# v2nixie.net
KiCad netlist of a schematic drawn in EAGLE
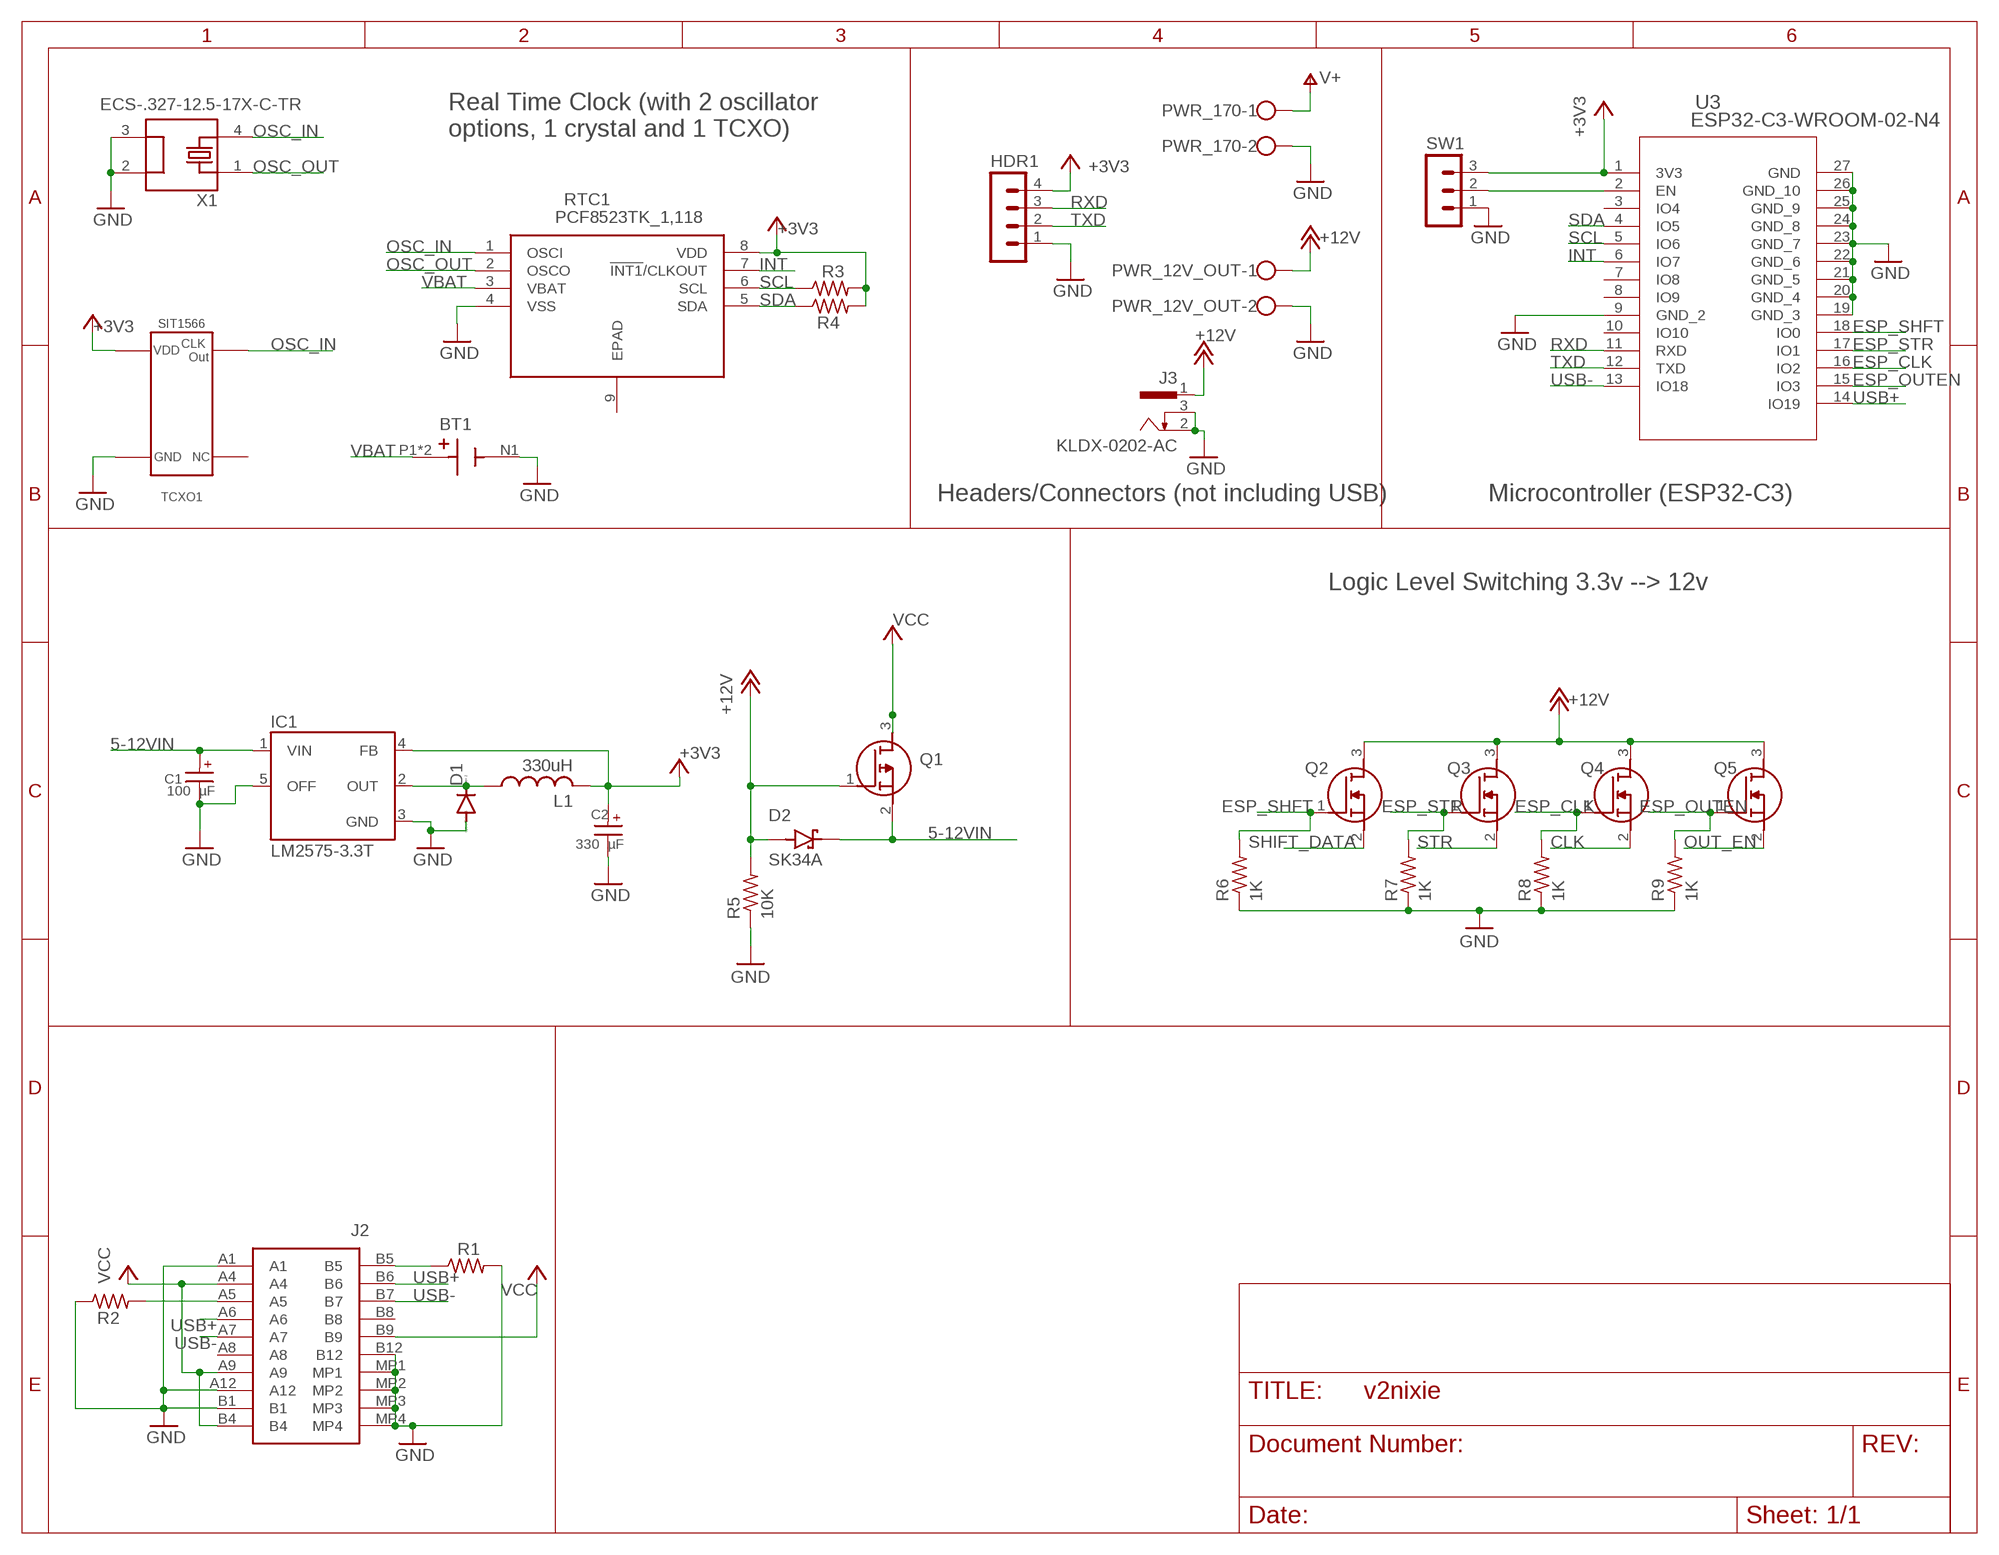
[diagram p0: schematic, sheet 1, part 1 of 2]
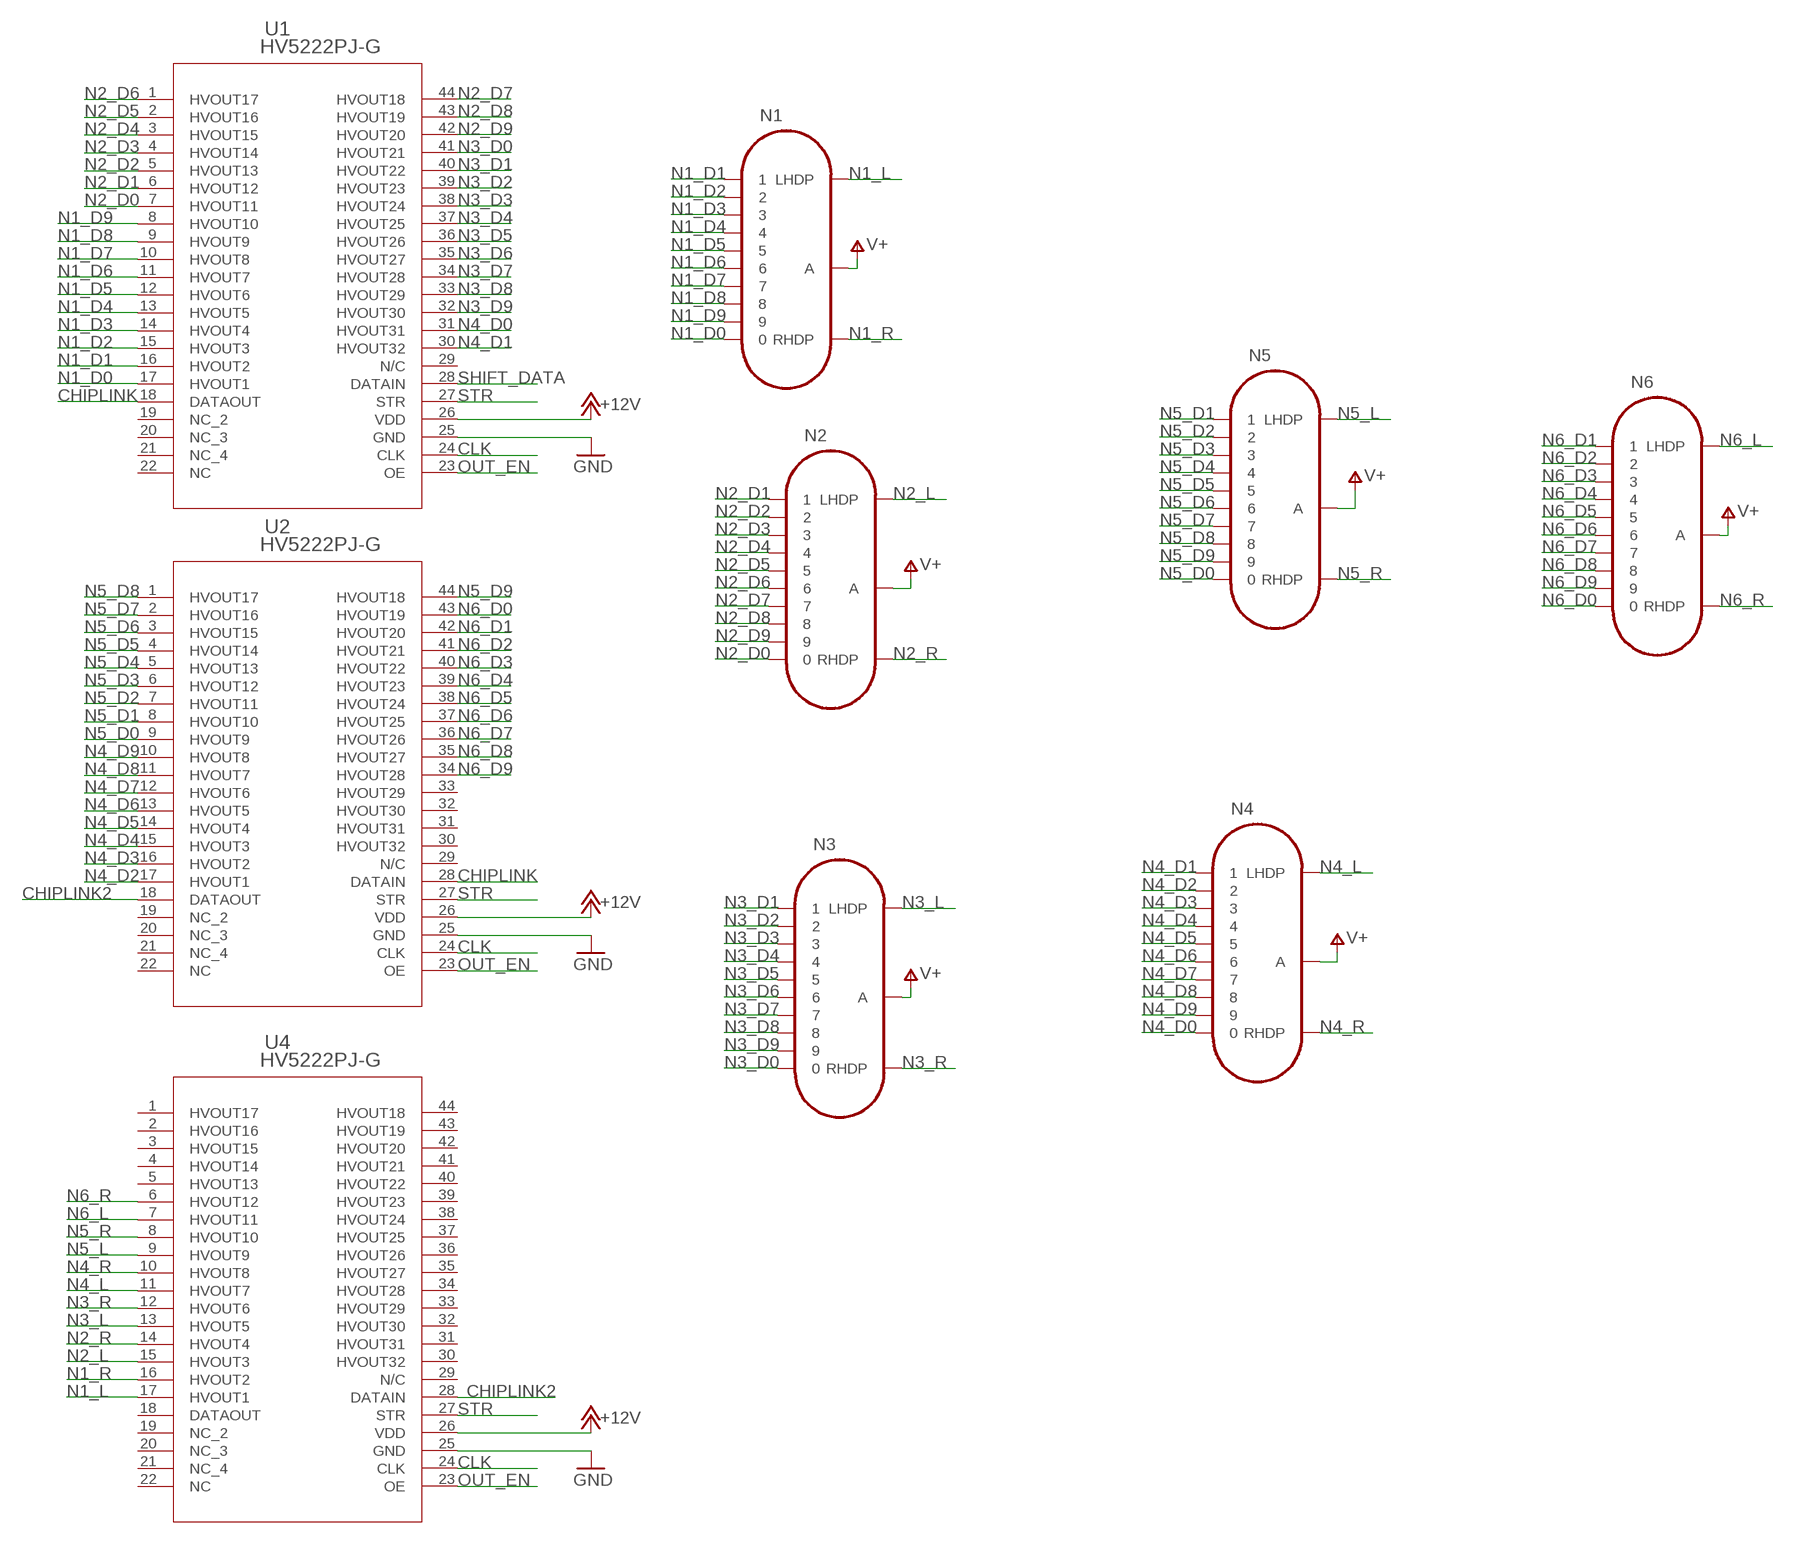
[diagram p1: schematic, sheet 1, part 2 of 2]

(export (version "E")
  (design (tool "Eeschema 10.0.6"))
  (components
    (comp (ref "BT1")
      (value "BAT-HLD-001-TR")
      (footprint "eagle-import:BAT_BAT-HLD-001-TR")
      (fields
        (field (name "DIGI-KEY_PART_NUMBER") "BAT-HLD-001-TRTR-ND")
        (field (name "MF") "Linx Technologies")
      )
      (libsource (lib "eagle-import") (part "BAT-HLD-001-TR"))
    )
    (comp (ref "C1")
      (value "100 µF")
      (footprint "eagle-import:WCAP-PTG5_8X11.5(DXL)")
      (libsource (lib "eagle-import") (part "WCAP-PTG5_8X11.5_870025374001"))
    )
    (comp (ref "C2")
      (value "330 µF")
      (footprint "eagle-import:WCAP-PTG5_8X8(DXL)")
      (libsource (lib "eagle-import") (part "WCAP-PTG5_8X8_870025174004"))
    )
    (comp (ref "D1")
      (value "DIODE-DO201-15")
      (footprint "eagle-import:DO201-15")
      (libsource (lib "eagle-import") (part "DIODE-DO201-15"))
    )
    (comp (ref "D2")
      (value "SK34A")
      (footprint "eagle-import:DIOM4325X250N")
      (fields (field (name "MF") "Taiwan Semiconductor") (field (name "MP") "SK34A-T"))
      (libsource (lib "eagle-import") (part "SK34A"))
    )
    (comp (ref "HDR1")
      (value "MA04-1")
      (footprint "eagle-import:MA04-1")
      (libsource (lib "eagle-import") (part "MA04-1"))
    )
    (comp (ref "IC1")
      (value "LM2575-3.3T")
      (footprint "eagle-import:TO220-5")
      (libsource (lib "eagle-import") (part "LM2575-3.3T"))
    )
    (comp (ref "J2")
      (value "USB4110-GF-A")
      (footprint "eagle-import:USB4110GFA")
      (fields (field (name "MOUSER_PART_NUMBER") "640-USB4110-GF-A"))
      (libsource (lib "eagle-import") (part "USB4110-GF-A"))
    )
    (comp (ref "J3")
      (value "KLDX-0202-AC")
      (footprint "eagle-import:KYCON_KLDX-0202-AC")
      (fields (field (name "DIGI-KEY_PART_NUMBER") "2092-KLDX-0202-AC-ND") (field (name "MF") "Kycon"))
      (libsource (lib "eagle-import") (part "KLDX-0202-AC"))
    )
    (comp (ref "L1")
      (value "330uH")
      (footprint "eagle-import:6000-XXXX-RC")
      (libsource (lib "eagle-import") (part "L-US6000-XXX-RC"))
    )
    (comp (ref "N1")
      (value "IN-14")
      (footprint "eagle-import:IN-14")
      (libsource (lib "eagle-import") (part "IN-14"))
    )
    (comp (ref "N2")
      (value "IN-14")
      (footprint "eagle-import:IN-14")
      (libsource (lib "eagle-import") (part "IN-14"))
    )
    (comp (ref "N3")
      (value "IN-14")
      (footprint "eagle-import:IN-14")
      (libsource (lib "eagle-import") (part "IN-14"))
    )
    (comp (ref "N4")
      (value "IN-14")
      (footprint "eagle-import:IN-14")
      (libsource (lib "eagle-import") (part "IN-14"))
    )
    (comp (ref "N5")
      (value "IN-14")
      (footprint "eagle-import:IN-14")
      (libsource (lib "eagle-import") (part "IN-14"))
    )
    (comp (ref "N6")
      (value "IN-14")
      (footprint "eagle-import:IN-14")
      (libsource (lib "eagle-import") (part "IN-14"))
    )
    (comp (ref "PWR_12V_OUT")
      (value "W237-102")
      (footprint "eagle-import:W237-102")
      (fields (field (name "MPN") "237-102") (field (name "SPICEPREFIX") "X"))
      (libsource (lib "eagle-import") (part "W237-102"))
    )
    (comp (ref "PWR_170")
      (value "W237-102")
      (footprint "eagle-import:W237-102")
      (fields (field (name "MPN") "237-102") (field (name "SPICEPREFIX") "X"))
      (libsource (lib "eagle-import") (part "W237-102"))
    )
    (comp (ref "Q1")
      (value "SSM3J117TU,LF_T")
      (footprint "eagle-import:SSM3J117TULFT")
      (fields (field (name "MANUFACTURER_PART_NUMBER") "SSM3J117TU,LF(T"))
      (libsource (lib "eagle-import") (part "SSM3J117TU,LF_T"))
    )
    (comp (ref "Q2")
      (value "RU1J002YNTCL")
      (footprint "eagle-import:SOTFL65P210X105-3N")
      (fields (field (name "MOUSER_PART_NUMBER") "755-RU1J002YNTCL"))
      (libsource (lib "eagle-import") (part "RU1J002YNTCL"))
    )
    (comp (ref "Q3")
      (value "RU1J002YNTCL")
      (footprint "eagle-import:SOTFL65P210X105-3N")
      (fields (field (name "MOUSER_PART_NUMBER") "755-RU1J002YNTCL"))
      (libsource (lib "eagle-import") (part "RU1J002YNTCL"))
    )
    (comp (ref "Q4")
      (value "RU1J002YNTCL")
      (footprint "eagle-import:SOTFL65P210X105-3N")
      (fields (field (name "MOUSER_PART_NUMBER") "755-RU1J002YNTCL"))
      (libsource (lib "eagle-import") (part "RU1J002YNTCL"))
    )
    (comp (ref "Q5")
      (value "RU1J002YNTCL")
      (footprint "eagle-import:SOTFL65P210X105-3N")
      (fields (field (name "MOUSER_PART_NUMBER") "755-RU1J002YNTCL"))
      (libsource (lib "eagle-import") (part "RU1J002YNTCL"))
    )
    (comp (ref "R1")
      (value "5.1K")
      (footprint "eagle-import:R0805")
      (libsource (lib "eagle-import") (part "R-US_R0805"))
    )
    (comp (ref "R2")
      (value "5.1K")
      (footprint "eagle-import:R0805")
      (libsource (lib "eagle-import") (part "R-US_R0805"))
    )
    (comp (ref "R3")
      (value "10K")
      (footprint "eagle-import:R0805")
      (libsource (lib "eagle-import") (part "R-US_R0805"))
    )
    (comp (ref "R4")
      (value "10K")
      (footprint "eagle-import:R0805")
      (libsource (lib "eagle-import") (part "R-US_R0805"))
    )
    (comp (ref "R5")
      (value "10K")
      (footprint "eagle-import:M0805")
      (libsource (lib "eagle-import") (part "resistor_348_R-US_M0805"))
    )
    (comp (ref "R6")
      (value "1K")
      (footprint "eagle-import:M0805")
      (libsource (lib "eagle-import") (part "resistor_348_R-US_M0805"))
    )
    (comp (ref "R7")
      (value "1K")
      (footprint "eagle-import:M0805")
      (libsource (lib "eagle-import") (part "resistor_348_R-US_M0805"))
    )
    (comp (ref "R8")
      (value "1K")
      (footprint "eagle-import:M0805")
      (libsource (lib "eagle-import") (part "resistor_348_R-US_M0805"))
    )
    (comp (ref "R9")
      (value "1K")
      (footprint "eagle-import:M0805")
      (libsource (lib "eagle-import") (part "resistor_348_R-US_M0805"))
    )
    (comp (ref "RTC1")
      (value "PCF8523TK_1,118")
      (footprint "eagle-import:SON80P400X400X100-9N")
      (fields
        (field (name "MANUFACTURER_PART_NUMBER") "PCF8523TK/1,118")
        (field (name "MOUSER_PART_NUMBER") "771-PCF8523TK/1118")
      )
      (libsource (lib "eagle-import") (part "PCF8523TK_1,118"))
    )
    (comp (ref "SW1")
      (value "MA03-1")
      (footprint "eagle-import:MA03-1")
      (libsource (lib "eagle-import") (part "MA03-1"))
    )
    (comp (ref "TCXO1")
      (value "SIT1566")
      (footprint "eagle-import:SIT1566")
      (libsource (lib "eagle-import") (part "SIT1566"))
    )
    (comp (ref "U1")
      (value "HV5222PJ-G")
      (footprint "eagle-import:PLCC44_MC_MCH")
      (fields (field (name "COPYRIGHT") "Copyright (C) 2022 Ultra Librarian. All rights reserved."))
      (libsource (lib "eagle-import") (part "HV5222PJ-G"))
    )
    (comp (ref "U2")
      (value "HV5222PJ-G")
      (footprint "eagle-import:PLCC44_MC_MCH")
      (fields (field (name "COPYRIGHT") "Copyright (C) 2022 Ultra Librarian. All rights reserved."))
      (libsource (lib "eagle-import") (part "HV5222PJ-G"))
    )
    (comp (ref "U3")
      (value "ESP32-C3-WROOM-02-N4")
      (footprint "eagle-import:IC18_ESP32-C3-WROOM-02-N4_EXP")
      (fields (field (name "COPYRIGHT") "Copyright (C) 2022 Ultra Librarian. All rights reserved."))
      (libsource (lib "eagle-import") (part "ESP32-C3-WROOM-02-N4"))
    )
    (comp (ref "U4")
      (value "HV5222PJ-G")
      (footprint "eagle-import:PLCC44_MC_MCH")
      (fields (field (name "COPYRIGHT") "Copyright (C) 2022 Ultra Librarian. All rights reserved."))
      (libsource (lib "eagle-import") (part "HV5222PJ-G"))
    )
    (comp (ref "X1")
      (value "ECS-.327-12.5-17X-C-TR")
      (footprint "eagle-import:XTAL_ECS-.327-12.5-17X-C-TR")
      (fields (field (name "DIGI-KEY_PART_NUMBER") "XC1912TR-ND") (field (name "MF") "ECS Inc."))
      (libsource (lib "eagle-import") (part "ECS-.327-12.5-17X-C-TR"))
    )
  )
  (nets
    (net (code "1") (name "+3V3") (class "Default")
      (node (ref "C2") (pin "1") (pinfunction "+_1") (pintype "passive"))
      (node (ref "HDR1") (pin "4") (pinfunction "4_4") (pintype "passive"))
      (node (ref "IC1") (pin "4") (pinfunction "FB_4") (pintype "input"))
      (node (ref "L1") (pin "2") (pinfunction "2_2") (pintype "passive"))
      (node (ref "R3") (pin "2") (pinfunction "2_2") (pintype "passive"))
      (node (ref "R4") (pin "2") (pinfunction "2_2") (pintype "passive"))
      (node (ref "RTC1") (pin "8") (pinfunction "VDD_8") (pintype "bidirectional"))
      (node (ref "SW1") (pin "3") (pinfunction "3_3") (pintype "passive"))
      (node (ref "TCXO1") (pin "VDD") (pinfunction "VDD_VDD") (pintype "power_in"))
      (node (ref "U3") (pin "1") (pinfunction "3V3_1") (pintype "passive"))
    )
    (net (code "2") (name "+12V") (class "Default")
      (node (ref "D2") (pin "A") (pinfunction "A_A") (pintype "passive"))
      (node (ref "J3") (pin "1") (pinfunction "1_1") (pintype "passive"))
      (node (ref "PWR_12V_OUT") (pin "1") (pinfunction "KL_1") (pintype "passive"))
      (node (ref "Q1") (pin "1") (pinfunction "G_1") (pintype "bidirectional"))
      (node (ref "Q2") (pin "3") (pinfunction "D_3") (pintype "bidirectional"))
      (node (ref "Q3") (pin "3") (pinfunction "D_3") (pintype "bidirectional"))
      (node (ref "Q4") (pin "3") (pinfunction "D_3") (pintype "bidirectional"))
      (node (ref "Q5") (pin "3") (pinfunction "D_3") (pintype "bidirectional"))
      (node (ref "R5") (pin "2") (pinfunction "2_2") (pintype "passive"))
      (node (ref "U1") (pin "26") (pinfunction "VDD_26") (pintype "power_in"))
      (node (ref "U2") (pin "26") (pinfunction "VDD_26") (pintype "power_in"))
      (node (ref "U4") (pin "26") (pinfunction "VDD_26") (pintype "power_in"))
    )
    (net (code "3") (name "/5-12VIN") (class "Default")
      (node (ref "C1") (pin "1") (pinfunction "+_1") (pintype "passive"))
      (node (ref "D2") (pin "C") (pinfunction "K_C") (pintype "passive"))
      (node (ref "IC1") (pin "1") (pinfunction "VIN_1") (pintype "power_in"))
      (node (ref "Q1") (pin "2") (pinfunction "S_2") (pintype "bidirectional"))
    )
    (net (code "4") (name "/CHIPLINK") (class "Default")
      (node (ref "U1") (pin "18") (pinfunction "DATAOUT_18") (pintype "output"))
      (node (ref "U2") (pin "28") (pinfunction "DATAIN_28") (pintype "input"))
    )
    (net (code "5") (name "/CHIPLINK2") (class "Default")
      (node (ref "U2") (pin "18") (pinfunction "DATAOUT_18") (pintype "output"))
      (node (ref "U4") (pin "28") (pinfunction "DATAIN_28") (pintype "input"))
    )
    (net (code "6") (name "/CLK") (class "Default")
      (node (ref "Q4") (pin "2") (pinfunction "S_2") (pintype "bidirectional"))
      (node (ref "U1") (pin "24") (pinfunction "CLK_24") (pintype "input"))
      (node (ref "U2") (pin "24") (pinfunction "CLK_24") (pintype "input"))
      (node (ref "U4") (pin "24") (pinfunction "CLK_24") (pintype "input"))
    )
    (net (code "7") (name "/ESP_CLK") (class "Default")
      (node (ref "Q4") (pin "1") (pinfunction "G_1") (pintype "bidirectional"))
      (node (ref "R8") (pin "2") (pinfunction "2_2") (pintype "passive"))
      (node (ref "U3") (pin "16") (pinfunction "IO2_16") (pintype "bidirectional"))
    )
    (net (code "8") (name "/ESP_OUTEN") (class "Default")
      (node (ref "Q5") (pin "1") (pinfunction "G_1") (pintype "bidirectional"))
      (node (ref "R9") (pin "2") (pinfunction "2_2") (pintype "passive"))
      (node (ref "U3") (pin "15") (pinfunction "IO3_15") (pintype "bidirectional"))
    )
    (net (code "9") (name "/ESP_SHFT") (class "Default")
      (node (ref "Q2") (pin "1") (pinfunction "G_1") (pintype "bidirectional"))
      (node (ref "R6") (pin "2") (pinfunction "2_2") (pintype "passive"))
      (node (ref "U3") (pin "18") (pinfunction "IO0_18") (pintype "bidirectional"))
    )
    (net (code "10") (name "/ESP_STR") (class "Default")
      (node (ref "Q3") (pin "1") (pinfunction "G_1") (pintype "bidirectional"))
      (node (ref "R7") (pin "2") (pinfunction "2_2") (pintype "passive"))
      (node (ref "U3") (pin "17") (pinfunction "IO1_17") (pintype "bidirectional"))
    )
    (net (code "11") (name "/INT") (class "Default")
      (node (ref "RTC1") (pin "7") (pinfunction "~{INT1}/CLKOUT_7") (pintype "bidirectional"))
      (node (ref "U3") (pin "6") (pinfunction "IO7_6") (pintype "bidirectional"))
    )
    (net (code "12") (name "/N1_D0") (class "Default")
      (node (ref "N1") (pin "0") (pinfunction "0_0") (pintype "bidirectional"))
      (node (ref "U1") (pin "17") (pinfunction "HVOUT1_17") (pintype "output"))
    )
    (net (code "13") (name "/N1_D1") (class "Default")
      (node (ref "N1") (pin "1") (pinfunction "1_1") (pintype "bidirectional"))
      (node (ref "U1") (pin "16") (pinfunction "HVOUT2_16") (pintype "output"))
    )
    (net (code "14") (name "/N1_D2") (class "Default")
      (node (ref "N1") (pin "2") (pinfunction "2_2") (pintype "bidirectional"))
      (node (ref "U1") (pin "15") (pinfunction "HVOUT3_15") (pintype "output"))
    )
    (net (code "15") (name "/N1_D3") (class "Default")
      (node (ref "N1") (pin "3") (pinfunction "3_3") (pintype "bidirectional"))
      (node (ref "U1") (pin "14") (pinfunction "HVOUT4_14") (pintype "output"))
    )
    (net (code "16") (name "/N1_D4") (class "Default")
      (node (ref "N1") (pin "4") (pinfunction "4_4") (pintype "bidirectional"))
      (node (ref "U1") (pin "13") (pinfunction "HVOUT5_13") (pintype "output"))
    )
    (net (code "17") (name "/N1_D5") (class "Default")
      (node (ref "N1") (pin "5") (pinfunction "5_5") (pintype "bidirectional"))
      (node (ref "U1") (pin "12") (pinfunction "HVOUT6_12") (pintype "output"))
    )
    (net (code "18") (name "/N1_D6") (class "Default")
      (node (ref "N1") (pin "6") (pinfunction "6_6") (pintype "bidirectional"))
      (node (ref "U1") (pin "11") (pinfunction "HVOUT7_11") (pintype "output"))
    )
    (net (code "19") (name "/N1_D7") (class "Default")
      (node (ref "N1") (pin "7") (pinfunction "7_7") (pintype "bidirectional"))
      (node (ref "U1") (pin "10") (pinfunction "HVOUT8_10") (pintype "output"))
    )
    (net (code "20") (name "/N1_D8") (class "Default")
      (node (ref "N1") (pin "8") (pinfunction "8_8") (pintype "bidirectional"))
      (node (ref "U1") (pin "9") (pinfunction "HVOUT9_9") (pintype "output"))
    )
    (net (code "21") (name "/N1_D9") (class "Default")
      (node (ref "N1") (pin "9") (pinfunction "9_9") (pintype "bidirectional"))
      (node (ref "U1") (pin "8") (pinfunction "HVOUT10_8") (pintype "output"))
    )
    (net (code "22") (name "/N1_L") (class "Default")
      (node (ref "N1") (pin "LHDP") (pinfunction "LHDP_LHDP") (pintype "bidirectional"))
      (node (ref "U4") (pin "17") (pinfunction "HVOUT1_17") (pintype "output"))
    )
    (net (code "23") (name "/N1_R") (class "Default")
      (node (ref "N1") (pin "RHDP") (pinfunction "RHDP_RHDP") (pintype "bidirectional"))
      (node (ref "U4") (pin "16") (pinfunction "HVOUT2_16") (pintype "output"))
    )
    (net (code "24") (name "/N2_D0") (class "Default")
      (node (ref "N2") (pin "0") (pinfunction "0_0") (pintype "bidirectional"))
      (node (ref "U1") (pin "7") (pinfunction "HVOUT11_7") (pintype "output"))
    )
    (net (code "25") (name "/N2_D1") (class "Default")
      (node (ref "N2") (pin "1") (pinfunction "1_1") (pintype "bidirectional"))
      (node (ref "U1") (pin "6") (pinfunction "HVOUT12_6") (pintype "output"))
    )
    (net (code "26") (name "/N2_D2") (class "Default")
      (node (ref "N2") (pin "2") (pinfunction "2_2") (pintype "bidirectional"))
      (node (ref "U1") (pin "5") (pinfunction "HVOUT13_5") (pintype "output"))
    )
    (net (code "27") (name "/N2_D3") (class "Default")
      (node (ref "N2") (pin "3") (pinfunction "3_3") (pintype "bidirectional"))
      (node (ref "U1") (pin "4") (pinfunction "HVOUT14_4") (pintype "output"))
    )
    (net (code "28") (name "/N2_D4") (class "Default")
      (node (ref "N2") (pin "4") (pinfunction "4_4") (pintype "bidirectional"))
      (node (ref "U1") (pin "3") (pinfunction "HVOUT15_3") (pintype "output"))
    )
    (net (code "29") (name "/N2_D5") (class "Default")
      (node (ref "N2") (pin "5") (pinfunction "5_5") (pintype "bidirectional"))
      (node (ref "U1") (pin "2") (pinfunction "HVOUT16_2") (pintype "output"))
    )
    (net (code "30") (name "/N2_D6") (class "Default")
      (node (ref "N2") (pin "6") (pinfunction "6_6") (pintype "bidirectional"))
      (node (ref "U1") (pin "1") (pinfunction "HVOUT17_1") (pintype "output"))
    )
    (net (code "31") (name "/N2_D7") (class "Default")
      (node (ref "N2") (pin "7") (pinfunction "7_7") (pintype "bidirectional"))
      (node (ref "U1") (pin "44") (pinfunction "HVOUT18_44") (pintype "output"))
    )
    (net (code "32") (name "/N2_D8") (class "Default")
      (node (ref "N2") (pin "8") (pinfunction "8_8") (pintype "bidirectional"))
      (node (ref "U1") (pin "43") (pinfunction "HVOUT19_43") (pintype "output"))
    )
    (net (code "33") (name "/N2_D9") (class "Default")
      (node (ref "N2") (pin "9") (pinfunction "9_9") (pintype "bidirectional"))
      (node (ref "U1") (pin "42") (pinfunction "HVOUT20_42") (pintype "output"))
    )
    (net (code "34") (name "/N2_L") (class "Default")
      (node (ref "N2") (pin "LHDP") (pinfunction "LHDP_LHDP") (pintype "bidirectional"))
      (node (ref "U4") (pin "15") (pinfunction "HVOUT3_15") (pintype "output"))
    )
    (net (code "35") (name "/N2_R") (class "Default")
      (node (ref "N2") (pin "RHDP") (pinfunction "RHDP_RHDP") (pintype "bidirectional"))
      (node (ref "U4") (pin "14") (pinfunction "HVOUT4_14") (pintype "output"))
    )
    (net (code "36") (name "/N3_D0") (class "Default")
      (node (ref "N3") (pin "0") (pinfunction "0_0") (pintype "bidirectional"))
      (node (ref "U1") (pin "41") (pinfunction "HVOUT21_41") (pintype "output"))
    )
    (net (code "37") (name "/N3_D1") (class "Default")
      (node (ref "N3") (pin "1") (pinfunction "1_1") (pintype "bidirectional"))
      (node (ref "U1") (pin "40") (pinfunction "HVOUT22_40") (pintype "output"))
    )
    (net (code "38") (name "/N3_D2") (class "Default")
      (node (ref "N3") (pin "2") (pinfunction "2_2") (pintype "bidirectional"))
      (node (ref "U1") (pin "39") (pinfunction "HVOUT23_39") (pintype "output"))
    )
    (net (code "39") (name "/N3_D3") (class "Default")
      (node (ref "N3") (pin "3") (pinfunction "3_3") (pintype "bidirectional"))
      (node (ref "U1") (pin "38") (pinfunction "HVOUT24_38") (pintype "output"))
    )
    (net (code "40") (name "/N3_D4") (class "Default")
      (node (ref "N3") (pin "4") (pinfunction "4_4") (pintype "bidirectional"))
      (node (ref "U1") (pin "37") (pinfunction "HVOUT25_37") (pintype "output"))
    )
    (net (code "41") (name "/N3_D5") (class "Default")
      (node (ref "N3") (pin "5") (pinfunction "5_5") (pintype "bidirectional"))
      (node (ref "U1") (pin "36") (pinfunction "HVOUT26_36") (pintype "output"))
    )
    (net (code "42") (name "/N3_D6") (class "Default")
      (node (ref "N3") (pin "6") (pinfunction "6_6") (pintype "bidirectional"))
      (node (ref "U1") (pin "35") (pinfunction "HVOUT27_35") (pintype "output"))
    )
    (net (code "43") (name "/N3_D7") (class "Default")
      (node (ref "N3") (pin "7") (pinfunction "7_7") (pintype "bidirectional"))
      (node (ref "U1") (pin "34") (pinfunction "HVOUT28_34") (pintype "output"))
    )
    (net (code "44") (name "/N3_D8") (class "Default")
      (node (ref "N3") (pin "8") (pinfunction "8_8") (pintype "bidirectional"))
      (node (ref "U1") (pin "33") (pinfunction "HVOUT29_33") (pintype "output"))
    )
    (net (code "45") (name "/N3_D9") (class "Default")
      (node (ref "N3") (pin "9") (pinfunction "9_9") (pintype "bidirectional"))
      (node (ref "U1") (pin "32") (pinfunction "HVOUT30_32") (pintype "output"))
    )
    (net (code "46") (name "/N3_L") (class "Default")
      (node (ref "N3") (pin "LHDP") (pinfunction "LHDP_LHDP") (pintype "bidirectional"))
      (node (ref "U4") (pin "13") (pinfunction "HVOUT5_13") (pintype "output"))
    )
    (net (code "47") (name "/N3_R") (class "Default")
      (node (ref "N3") (pin "RHDP") (pinfunction "RHDP_RHDP") (pintype "bidirectional"))
      (node (ref "U4") (pin "12") (pinfunction "HVOUT6_12") (pintype "output"))
    )
    (net (code "48") (name "/N4_D0") (class "Default")
      (node (ref "N4") (pin "0") (pinfunction "0_0") (pintype "bidirectional"))
      (node (ref "U1") (pin "31") (pinfunction "HVOUT31_31") (pintype "output"))
    )
    (net (code "49") (name "/N4_D1") (class "Default")
      (node (ref "N4") (pin "1") (pinfunction "1_1") (pintype "bidirectional"))
      (node (ref "U1") (pin "30") (pinfunction "HVOUT32_30") (pintype "output"))
    )
    (net (code "50") (name "/N4_D2") (class "Default")
      (node (ref "N4") (pin "2") (pinfunction "2_2") (pintype "bidirectional"))
      (node (ref "U2") (pin "17") (pinfunction "HVOUT1_17") (pintype "output"))
    )
    (net (code "51") (name "/N4_D3") (class "Default")
      (node (ref "N4") (pin "3") (pinfunction "3_3") (pintype "bidirectional"))
      (node (ref "U2") (pin "16") (pinfunction "HVOUT2_16") (pintype "output"))
    )
    (net (code "52") (name "/N4_D4") (class "Default")
      (node (ref "N4") (pin "4") (pinfunction "4_4") (pintype "bidirectional"))
      (node (ref "U2") (pin "15") (pinfunction "HVOUT3_15") (pintype "output"))
    )
    (net (code "53") (name "/N4_D5") (class "Default")
      (node (ref "N4") (pin "5") (pinfunction "5_5") (pintype "bidirectional"))
      (node (ref "U2") (pin "14") (pinfunction "HVOUT4_14") (pintype "output"))
    )
    (net (code "54") (name "/N4_D6") (class "Default")
      (node (ref "N4") (pin "6") (pinfunction "6_6") (pintype "bidirectional"))
      (node (ref "U2") (pin "13") (pinfunction "HVOUT5_13") (pintype "output"))
    )
    (net (code "55") (name "/N4_D7") (class "Default")
      (node (ref "N4") (pin "7") (pinfunction "7_7") (pintype "bidirectional"))
      (node (ref "U2") (pin "12") (pinfunction "HVOUT6_12") (pintype "output"))
    )
    (net (code "56") (name "/N4_D8") (class "Default")
      (node (ref "N4") (pin "8") (pinfunction "8_8") (pintype "bidirectional"))
      (node (ref "U2") (pin "11") (pinfunction "HVOUT7_11") (pintype "output"))
    )
    (net (code "57") (name "/N4_D9") (class "Default")
      (node (ref "N4") (pin "9") (pinfunction "9_9") (pintype "bidirectional"))
      (node (ref "U2") (pin "10") (pinfunction "HVOUT8_10") (pintype "output"))
    )
    (net (code "58") (name "/N4_L") (class "Default")
      (node (ref "N4") (pin "LHDP") (pinfunction "LHDP_LHDP") (pintype "bidirectional"))
      (node (ref "U4") (pin "11") (pinfunction "HVOUT7_11") (pintype "output"))
    )
    (net (code "59") (name "/N4_R") (class "Default")
      (node (ref "N4") (pin "RHDP") (pinfunction "RHDP_RHDP") (pintype "bidirectional"))
      (node (ref "U4") (pin "10") (pinfunction "HVOUT8_10") (pintype "output"))
    )
    (net (code "60") (name "/N5_D0") (class "Default")
      (node (ref "N5") (pin "0") (pinfunction "0_0") (pintype "bidirectional"))
      (node (ref "U2") (pin "9") (pinfunction "HVOUT9_9") (pintype "output"))
    )
    (net (code "61") (name "/N5_D1") (class "Default")
      (node (ref "N5") (pin "1") (pinfunction "1_1") (pintype "bidirectional"))
      (node (ref "U2") (pin "8") (pinfunction "HVOUT10_8") (pintype "output"))
    )
    (net (code "62") (name "/N5_D2") (class "Default")
      (node (ref "N5") (pin "2") (pinfunction "2_2") (pintype "bidirectional"))
      (node (ref "U2") (pin "7") (pinfunction "HVOUT11_7") (pintype "output"))
    )
    (net (code "63") (name "/N5_D3") (class "Default")
      (node (ref "N5") (pin "3") (pinfunction "3_3") (pintype "bidirectional"))
      (node (ref "U2") (pin "6") (pinfunction "HVOUT12_6") (pintype "output"))
    )
    (net (code "64") (name "/N5_D4") (class "Default")
      (node (ref "N5") (pin "4") (pinfunction "4_4") (pintype "bidirectional"))
      (node (ref "U2") (pin "5") (pinfunction "HVOUT13_5") (pintype "output"))
    )
    (net (code "65") (name "/N5_D5") (class "Default")
      (node (ref "N5") (pin "5") (pinfunction "5_5") (pintype "bidirectional"))
      (node (ref "U2") (pin "4") (pinfunction "HVOUT14_4") (pintype "output"))
    )
    (net (code "66") (name "/N5_D6") (class "Default")
      (node (ref "N5") (pin "6") (pinfunction "6_6") (pintype "bidirectional"))
      (node (ref "U2") (pin "3") (pinfunction "HVOUT15_3") (pintype "output"))
    )
    (net (code "67") (name "/N5_D7") (class "Default")
      (node (ref "N5") (pin "7") (pinfunction "7_7") (pintype "bidirectional"))
      (node (ref "U2") (pin "2") (pinfunction "HVOUT16_2") (pintype "output"))
    )
    (net (code "68") (name "/N5_D8") (class "Default")
      (node (ref "N5") (pin "8") (pinfunction "8_8") (pintype "bidirectional"))
      (node (ref "U2") (pin "1") (pinfunction "HVOUT17_1") (pintype "output"))
    )
    (net (code "69") (name "/N5_D9") (class "Default")
      (node (ref "N5") (pin "9") (pinfunction "9_9") (pintype "bidirectional"))
      (node (ref "U2") (pin "44") (pinfunction "HVOUT18_44") (pintype "output"))
    )
    (net (code "70") (name "/N5_L") (class "Default")
      (node (ref "N5") (pin "LHDP") (pinfunction "LHDP_LHDP") (pintype "bidirectional"))
      (node (ref "U4") (pin "9") (pinfunction "HVOUT9_9") (pintype "output"))
    )
    (net (code "71") (name "/N5_R") (class "Default")
      (node (ref "N5") (pin "RHDP") (pinfunction "RHDP_RHDP") (pintype "bidirectional"))
      (node (ref "U4") (pin "8") (pinfunction "HVOUT10_8") (pintype "output"))
    )
    (net (code "72") (name "/N6_D0") (class "Default")
      (node (ref "N6") (pin "0") (pinfunction "0_0") (pintype "bidirectional"))
      (node (ref "U2") (pin "43") (pinfunction "HVOUT19_43") (pintype "output"))
    )
    (net (code "73") (name "/N6_D1") (class "Default")
      (node (ref "N6") (pin "1") (pinfunction "1_1") (pintype "bidirectional"))
      (node (ref "U2") (pin "42") (pinfunction "HVOUT20_42") (pintype "output"))
    )
    (net (code "74") (name "/N6_D2") (class "Default")
      (node (ref "N6") (pin "2") (pinfunction "2_2") (pintype "bidirectional"))
      (node (ref "U2") (pin "41") (pinfunction "HVOUT21_41") (pintype "output"))
    )
    (net (code "75") (name "/N6_D3") (class "Default")
      (node (ref "N6") (pin "3") (pinfunction "3_3") (pintype "bidirectional"))
      (node (ref "U2") (pin "40") (pinfunction "HVOUT22_40") (pintype "output"))
    )
    (net (code "76") (name "/N6_D4") (class "Default")
      (node (ref "N6") (pin "4") (pinfunction "4_4") (pintype "bidirectional"))
      (node (ref "U2") (pin "39") (pinfunction "HVOUT23_39") (pintype "output"))
    )
    (net (code "77") (name "/N6_D5") (class "Default")
      (node (ref "N6") (pin "5") (pinfunction "5_5") (pintype "bidirectional"))
      (node (ref "U2") (pin "38") (pinfunction "HVOUT24_38") (pintype "output"))
    )
    (net (code "78") (name "/N6_D6") (class "Default")
      (node (ref "N6") (pin "6") (pinfunction "6_6") (pintype "bidirectional"))
      (node (ref "U2") (pin "37") (pinfunction "HVOUT25_37") (pintype "output"))
    )
    (net (code "79") (name "/N6_D7") (class "Default")
      (node (ref "N6") (pin "7") (pinfunction "7_7") (pintype "bidirectional"))
      (node (ref "U2") (pin "36") (pinfunction "HVOUT26_36") (pintype "output"))
    )
    (net (code "80") (name "/N6_D8") (class "Default")
      (node (ref "N6") (pin "8") (pinfunction "8_8") (pintype "bidirectional"))
      (node (ref "U2") (pin "35") (pinfunction "HVOUT27_35") (pintype "output"))
    )
    (net (code "81") (name "/N6_D9") (class "Default")
      (node (ref "N6") (pin "9") (pinfunction "9_9") (pintype "bidirectional"))
      (node (ref "U2") (pin "34") (pinfunction "HVOUT28_34") (pintype "output"))
    )
    (net (code "82") (name "/N6_L") (class "Default")
      (node (ref "N6") (pin "LHDP") (pinfunction "LHDP_LHDP") (pintype "bidirectional"))
      (node (ref "U4") (pin "7") (pinfunction "HVOUT11_7") (pintype "output"))
    )
    (net (code "83") (name "/N6_R") (class "Default")
      (node (ref "N6") (pin "RHDP") (pinfunction "RHDP_RHDP") (pintype "bidirectional"))
      (node (ref "U4") (pin "6") (pinfunction "HVOUT12_6") (pintype "output"))
    )
    (net (code "84") (name "/OSC_IN") (class "Default")
      (node (ref "RTC1") (pin "1") (pinfunction "OSCI_1") (pintype "bidirectional"))
      (node (ref "TCXO1") (pin "CLK_OUT") (pinfunction "CLK_OUT_CLK_OUT") (pintype "output"))
      (node (ref "X1") (pin "4") (pinfunction "4_4") (pintype "passive"))
    )
    (net (code "85") (name "/OSC_OUT") (class "Default")
      (node (ref "RTC1") (pin "2") (pinfunction "OSCO_2") (pintype "bidirectional"))
      (node (ref "X1") (pin "1") (pinfunction "1_1") (pintype "passive"))
    )
    (net (code "86") (name "/OUT_EN") (class "Default")
      (node (ref "Q5") (pin "2") (pinfunction "S_2") (pintype "bidirectional"))
      (node (ref "U1") (pin "23") (pinfunction "OE_23") (pintype "bidirectional"))
      (node (ref "U2") (pin "23") (pinfunction "OE_23") (pintype "bidirectional"))
      (node (ref "U4") (pin "23") (pinfunction "OE_23") (pintype "bidirectional"))
    )
    (net (code "87") (name "/RXD") (class "Default")
      (node (ref "HDR1") (pin "3") (pinfunction "3_3") (pintype "passive"))
      (node (ref "U3") (pin "11") (pinfunction "RXD_11") (pintype "passive"))
    )
    (net (code "88") (name "/SCL") (class "Default")
      (node (ref "R3") (pin "1") (pinfunction "1_1") (pintype "passive"))
      (node (ref "RTC1") (pin "6") (pinfunction "SCL_6") (pintype "bidirectional"))
      (node (ref "U3") (pin "5") (pinfunction "IO6_5") (pintype "bidirectional"))
    )
    (net (code "89") (name "/SDA") (class "Default")
      (node (ref "R4") (pin "1") (pinfunction "1_1") (pintype "passive"))
      (node (ref "RTC1") (pin "5") (pinfunction "SDA_5") (pintype "bidirectional"))
      (node (ref "U3") (pin "4") (pinfunction "IO5_4") (pintype "bidirectional"))
    )
    (net (code "90") (name "/SHIFT_DATA") (class "Default")
      (node (ref "Q2") (pin "2") (pinfunction "S_2") (pintype "bidirectional"))
      (node (ref "U1") (pin "28") (pinfunction "DATAIN_28") (pintype "input"))
    )
    (net (code "91") (name "/STR") (class "Default")
      (node (ref "Q3") (pin "2") (pinfunction "S_2") (pintype "bidirectional"))
      (node (ref "U1") (pin "27") (pinfunction "STR_27") (pintype "passive"))
      (node (ref "U2") (pin "27") (pinfunction "STR_27") (pintype "passive"))
      (node (ref "U4") (pin "27") (pinfunction "STR_27") (pintype "passive"))
    )
    (net (code "92") (name "/TXD") (class "Default")
      (node (ref "HDR1") (pin "2") (pinfunction "2_2") (pintype "passive"))
      (node (ref "U3") (pin "12") (pinfunction "TXD_12") (pintype "passive"))
    )
    (net (code "93") (name "/USB+") (class "Default")
      (node (ref "J2") (pin "A6") (pinfunction "A6_A6") (pintype "bidirectional"))
      (node (ref "J2") (pin "B6") (pinfunction "B6_B6") (pintype "bidirectional"))
      (node (ref "U3") (pin "14") (pinfunction "IO19_14") (pintype "bidirectional"))
    )
    (net (code "94") (name "/USB-") (class "Default")
      (node (ref "J2") (pin "A7") (pinfunction "A7_A7") (pintype "bidirectional"))
      (node (ref "J2") (pin "B7") (pinfunction "B7_B7") (pintype "bidirectional"))
      (node (ref "U3") (pin "13") (pinfunction "IO18_13") (pintype "bidirectional"))
    )
    (net (code "95") (name "/VBAT") (class "Default")
      (node (ref "BT1") (pin "P1") (pinfunction "+_P1") (pintype "passive"))
      (node (ref "BT1") (pin "P2") (pinfunction "+_P2") (pintype "passive"))
      (node (ref "RTC1") (pin "3") (pinfunction "VBAT_3") (pintype "bidirectional"))
    )
    (net (code "96") (name "GND") (class "Default")
      (node (ref "BT1") (pin "N1") (pinfunction "-_N1") (pintype "passive"))
      (node (ref "C1") (pin "2") (pinfunction "-_2") (pintype "passive"))
      (node (ref "C2") (pin "2") (pinfunction "-_2") (pintype "passive"))
      (node (ref "D1") (pin "A") (pinfunction "A_A") (pintype "passive"))
      (node (ref "HDR1") (pin "1") (pinfunction "1_1") (pintype "passive"))
      (node (ref "IC1") (pin "3") (pinfunction "GND_3") (pintype "power_in"))
      (node (ref "IC1") (pin "5") (pinfunction "OFF_5") (pintype "input"))
      (node (ref "J2") (pin "A1") (pinfunction "A1_A1") (pintype "bidirectional"))
      (node (ref "J2") (pin "A12") (pinfunction "A12_A12") (pintype "bidirectional"))
      (node (ref "J2") (pin "B1") (pinfunction "B1_B1") (pintype "bidirectional"))
      (node (ref "J2") (pin "B12") (pinfunction "B12_B12") (pintype "bidirectional"))
      (node (ref "J2") (pin "MP1") (pinfunction "MP1_MP1") (pintype "bidirectional"))
      (node (ref "J2") (pin "MP2") (pinfunction "MP2_MP2") (pintype "bidirectional"))
      (node (ref "J2") (pin "MP3") (pinfunction "MP3_MP3") (pintype "bidirectional"))
      (node (ref "J2") (pin "MP4") (pinfunction "MP4_MP4") (pintype "bidirectional"))
      (node (ref "J3") (pin "2") (pinfunction "2_2") (pintype "passive"))
      (node (ref "J3") (pin "3") (pinfunction "3_3") (pintype "passive"))
      (node (ref "PWR_12V_OUT") (pin "2") (pinfunction "KL_2") (pintype "passive"))
      (node (ref "PWR_170") (pin "2") (pinfunction "KL_2") (pintype "passive"))
      (node (ref "R1") (pin "2") (pinfunction "2_2") (pintype "passive"))
      (node (ref "R2") (pin "1") (pinfunction "1_1") (pintype "passive"))
      (node (ref "R5") (pin "1") (pinfunction "1_1") (pintype "passive"))
      (node (ref "R6") (pin "1") (pinfunction "1_1") (pintype "passive"))
      (node (ref "R7") (pin "1") (pinfunction "1_1") (pintype "passive"))
      (node (ref "R8") (pin "1") (pinfunction "1_1") (pintype "passive"))
      (node (ref "R9") (pin "1") (pinfunction "1_1") (pintype "passive"))
      (node (ref "RTC1") (pin "4") (pinfunction "VSS_4") (pintype "bidirectional"))
      (node (ref "SW1") (pin "1") (pinfunction "1_1") (pintype "passive"))
      (node (ref "TCXO1") (pin "GND") (pinfunction "GND_GND") (pintype "power_in"))
      (node (ref "U1") (pin "25") (pinfunction "GND_25") (pintype "passive"))
      (node (ref "U2") (pin "25") (pinfunction "GND_25") (pintype "passive"))
      (node (ref "U3") (pin "19") (pinfunction "GND_3_19") (pintype "passive"))
      (node (ref "U3") (pin "20") (pinfunction "GND_4_20") (pintype "passive"))
      (node (ref "U3") (pin "21") (pinfunction "GND_5_21") (pintype "passive"))
      (node (ref "U3") (pin "22") (pinfunction "GND_6_22") (pintype "passive"))
      (node (ref "U3") (pin "23") (pinfunction "GND_7_23") (pintype "passive"))
      (node (ref "U3") (pin "24") (pinfunction "GND_8_24") (pintype "passive"))
      (node (ref "U3") (pin "25") (pinfunction "GND_9_25") (pintype "passive"))
      (node (ref "U3") (pin "26") (pinfunction "GND_10_26") (pintype "passive"))
      (node (ref "U3") (pin "27") (pinfunction "GND_27") (pintype "passive"))
      (node (ref "U3") (pin "9") (pinfunction "GND_2_9") (pintype "passive"))
      (node (ref "U4") (pin "25") (pinfunction "GND_25") (pintype "passive"))
      (node (ref "X1") (pin "2") (pinfunction "2_2") (pintype "passive"))
      (node (ref "X1") (pin "3") (pinfunction "3_3") (pintype "passive"))
    )
    (net (code "97") (name "Net-(IC1-OUT)") (class "Default")
      (node (ref "D1") (pin "C") (pinfunction "C_C") (pintype "passive"))
      (node (ref "IC1") (pin "2") (pinfunction "OUT_2") (pintype "output"))
      (node (ref "L1") (pin "1") (pinfunction "1_1") (pintype "passive"))
    )
    (net (code "98") (name "Net-(J2-PadA5)") (class "Default")
      (node (ref "J2") (pin "A5") (pinfunction "A5_A5") (pintype "bidirectional"))
      (node (ref "R2") (pin "2") (pinfunction "2_2") (pintype "passive"))
    )
    (net (code "99") (name "Net-(J2-PadB5)") (class "Default")
      (node (ref "J2") (pin "B5") (pinfunction "B5_B5") (pintype "bidirectional"))
      (node (ref "R1") (pin "1") (pinfunction "1_1") (pintype "passive"))
    )
    (net (code "100") (name "Net-(U3-EN)") (class "Default")
      (node (ref "SW1") (pin "2") (pinfunction "2_2") (pintype "passive"))
      (node (ref "U3") (pin "2") (pinfunction "EN_2") (pintype "passive"))
    )
    (net (code "101") (name "V+") (class "Default")
      (node (ref "N1") (pin "A") (pinfunction "A_A") (pintype "bidirectional"))
      (node (ref "N2") (pin "A") (pinfunction "A_A") (pintype "bidirectional"))
      (node (ref "N3") (pin "A") (pinfunction "A_A") (pintype "bidirectional"))
      (node (ref "N4") (pin "A") (pinfunction "A_A") (pintype "bidirectional"))
      (node (ref "N5") (pin "A") (pinfunction "A_A") (pintype "bidirectional"))
      (node (ref "N6") (pin "A") (pinfunction "A_A") (pintype "bidirectional"))
      (node (ref "PWR_170") (pin "1") (pinfunction "KL_1") (pintype "passive"))
    )
    (net (code "102") (name "VCC") (class "Default")
      (node (ref "J2") (pin "A4") (pinfunction "A4_A4") (pintype "bidirectional"))
      (node (ref "J2") (pin "A9") (pinfunction "A9_A9") (pintype "bidirectional"))
      (node (ref "J2") (pin "B4") (pinfunction "B4_B4") (pintype "bidirectional"))
      (node (ref "J2") (pin "B9") (pinfunction "B9_B9") (pintype "bidirectional"))
      (node (ref "Q1") (pin "3") (pinfunction "D_3") (pintype "bidirectional"))
    )
    (net (code "103") (name "unconnected-(J2-PadA8)") (class "Default")
      (node (ref "J2") (pin "A8") (pinfunction "A8_A8") (pintype "bidirectional"))
    )
    (net (code "104") (name "unconnected-(J2-PadB8)") (class "Default")
      (node (ref "J2") (pin "B8") (pinfunction "B8_B8") (pintype "bidirectional"))
    )
    (net (code "105") (name "unconnected-(RTC1-EPAD-Pad9)") (class "Default")
      (node (ref "RTC1") (pin "9") (pinfunction "EPAD_9") (pintype "bidirectional"))
    )
    (net (code "106") (name "unconnected-(TCXO1-PadNC)") (class "Default")
      (node (ref "TCXO1") (pin "NC") (pinfunction "NC_NC") (pintype "no_connect"))
    )
    (net (code "107") (name "unconnected-(U1-NC-Pad22)") (class "Default")
      (node (ref "U1") (pin "22") (pinfunction "NC_22") (pintype "no_connect"))
    )
    (net (code "108") (name "unconnected-(U1-NC_2-Pad19)") (class "Default")
      (node (ref "U1") (pin "19") (pinfunction "NC_2_19") (pintype "no_connect"))
    )
    (net (code "109") (name "unconnected-(U1-NC_3-Pad20)") (class "Default")
      (node (ref "U1") (pin "20") (pinfunction "NC_3_20") (pintype "no_connect"))
    )
    (net (code "110") (name "unconnected-(U1-NC_4-Pad21)") (class "Default")
      (node (ref "U1") (pin "21") (pinfunction "NC_4_21") (pintype "no_connect"))
    )
    (net (code "111") (name "unconnected-(U1-N{slash}C-Pad29)") (class "Default")
      (node (ref "U1") (pin "29") (pinfunction "N/C_29") (pintype "no_connect"))
    )
    (net (code "112") (name "unconnected-(U2-HVOUT29-Pad33)") (class "Default")
      (node (ref "U2") (pin "33") (pinfunction "HVOUT29_33") (pintype "output"))
    )
    (net (code "113") (name "unconnected-(U2-HVOUT30-Pad32)") (class "Default")
      (node (ref "U2") (pin "32") (pinfunction "HVOUT30_32") (pintype "output"))
    )
    (net (code "114") (name "unconnected-(U2-HVOUT31-Pad31)") (class "Default")
      (node (ref "U2") (pin "31") (pinfunction "HVOUT31_31") (pintype "output"))
    )
    (net (code "115") (name "unconnected-(U2-HVOUT32-Pad30)") (class "Default")
      (node (ref "U2") (pin "30") (pinfunction "HVOUT32_30") (pintype "output"))
    )
    (net (code "116") (name "unconnected-(U2-NC-Pad22)") (class "Default")
      (node (ref "U2") (pin "22") (pinfunction "NC_22") (pintype "no_connect"))
    )
    (net (code "117") (name "unconnected-(U2-NC_2-Pad19)") (class "Default")
      (node (ref "U2") (pin "19") (pinfunction "NC_2_19") (pintype "no_connect"))
    )
    (net (code "118") (name "unconnected-(U2-NC_3-Pad20)") (class "Default")
      (node (ref "U2") (pin "20") (pinfunction "NC_3_20") (pintype "no_connect"))
    )
    (net (code "119") (name "unconnected-(U2-NC_4-Pad21)") (class "Default")
      (node (ref "U2") (pin "21") (pinfunction "NC_4_21") (pintype "no_connect"))
    )
    (net (code "120") (name "unconnected-(U2-N{slash}C-Pad29)") (class "Default")
      (node (ref "U2") (pin "29") (pinfunction "N/C_29") (pintype "no_connect"))
    )
    (net (code "121") (name "unconnected-(U3-IO4-Pad3)") (class "Default")
      (node (ref "U3") (pin "3") (pinfunction "IO4_3") (pintype "bidirectional"))
    )
    (net (code "122") (name "unconnected-(U3-IO8-Pad7)") (class "Default")
      (node (ref "U3") (pin "7") (pinfunction "IO8_7") (pintype "bidirectional"))
    )
    (net (code "123") (name "unconnected-(U3-IO9-Pad8)") (class "Default")
      (node (ref "U3") (pin "8") (pinfunction "IO9_8") (pintype "bidirectional"))
    )
    (net (code "124") (name "unconnected-(U3-IO10-Pad10)") (class "Default")
      (node (ref "U3") (pin "10") (pinfunction "IO10_10") (pintype "bidirectional"))
    )
    (net (code "125") (name "unconnected-(U4-DATAOUT-Pad18)") (class "Default")
      (node (ref "U4") (pin "18") (pinfunction "DATAOUT_18") (pintype "output"))
    )
    (net (code "126") (name "unconnected-(U4-HVOUT13-Pad5)") (class "Default")
      (node (ref "U4") (pin "5") (pinfunction "HVOUT13_5") (pintype "output"))
    )
    (net (code "127") (name "unconnected-(U4-HVOUT14-Pad4)") (class "Default")
      (node (ref "U4") (pin "4") (pinfunction "HVOUT14_4") (pintype "output"))
    )
    (net (code "128") (name "unconnected-(U4-HVOUT15-Pad3)") (class "Default")
      (node (ref "U4") (pin "3") (pinfunction "HVOUT15_3") (pintype "output"))
    )
    (net (code "129") (name "unconnected-(U4-HVOUT16-Pad2)") (class "Default")
      (node (ref "U4") (pin "2") (pinfunction "HVOUT16_2") (pintype "output"))
    )
    (net (code "130") (name "unconnected-(U4-HVOUT17-Pad1)") (class "Default")
      (node (ref "U4") (pin "1") (pinfunction "HVOUT17_1") (pintype "output"))
    )
    (net (code "131") (name "unconnected-(U4-HVOUT18-Pad44)") (class "Default")
      (node (ref "U4") (pin "44") (pinfunction "HVOUT18_44") (pintype "output"))
    )
    (net (code "132") (name "unconnected-(U4-HVOUT19-Pad43)") (class "Default")
      (node (ref "U4") (pin "43") (pinfunction "HVOUT19_43") (pintype "output"))
    )
    (net (code "133") (name "unconnected-(U4-HVOUT20-Pad42)") (class "Default")
      (node (ref "U4") (pin "42") (pinfunction "HVOUT20_42") (pintype "output"))
    )
    (net (code "134") (name "unconnected-(U4-HVOUT21-Pad41)") (class "Default")
      (node (ref "U4") (pin "41") (pinfunction "HVOUT21_41") (pintype "output"))
    )
    (net (code "135") (name "unconnected-(U4-HVOUT22-Pad40)") (class "Default")
      (node (ref "U4") (pin "40") (pinfunction "HVOUT22_40") (pintype "output"))
    )
    (net (code "136") (name "unconnected-(U4-HVOUT23-Pad39)") (class "Default")
      (node (ref "U4") (pin "39") (pinfunction "HVOUT23_39") (pintype "output"))
    )
    (net (code "137") (name "unconnected-(U4-HVOUT24-Pad38)") (class "Default")
      (node (ref "U4") (pin "38") (pinfunction "HVOUT24_38") (pintype "output"))
    )
    (net (code "138") (name "unconnected-(U4-HVOUT25-Pad37)") (class "Default")
      (node (ref "U4") (pin "37") (pinfunction "HVOUT25_37") (pintype "output"))
    )
    (net (code "139") (name "unconnected-(U4-HVOUT26-Pad36)") (class "Default")
      (node (ref "U4") (pin "36") (pinfunction "HVOUT26_36") (pintype "output"))
    )
    (net (code "140") (name "unconnected-(U4-HVOUT27-Pad35)") (class "Default")
      (node (ref "U4") (pin "35") (pinfunction "HVOUT27_35") (pintype "output"))
    )
    (net (code "141") (name "unconnected-(U4-HVOUT28-Pad34)") (class "Default")
      (node (ref "U4") (pin "34") (pinfunction "HVOUT28_34") (pintype "output"))
    )
    (net (code "142") (name "unconnected-(U4-HVOUT29-Pad33)") (class "Default")
      (node (ref "U4") (pin "33") (pinfunction "HVOUT29_33") (pintype "output"))
    )
    (net (code "143") (name "unconnected-(U4-HVOUT30-Pad32)") (class "Default")
      (node (ref "U4") (pin "32") (pinfunction "HVOUT30_32") (pintype "output"))
    )
    (net (code "144") (name "unconnected-(U4-HVOUT31-Pad31)") (class "Default")
      (node (ref "U4") (pin "31") (pinfunction "HVOUT31_31") (pintype "output"))
    )
    (net (code "145") (name "unconnected-(U4-HVOUT32-Pad30)") (class "Default")
      (node (ref "U4") (pin "30") (pinfunction "HVOUT32_30") (pintype "output"))
    )
    (net (code "146") (name "unconnected-(U4-NC-Pad22)") (class "Default")
      (node (ref "U4") (pin "22") (pinfunction "NC_22") (pintype "no_connect"))
    )
    (net (code "147") (name "unconnected-(U4-NC_2-Pad19)") (class "Default")
      (node (ref "U4") (pin "19") (pinfunction "NC_2_19") (pintype "no_connect"))
    )
    (net (code "148") (name "unconnected-(U4-NC_3-Pad20)") (class "Default")
      (node (ref "U4") (pin "20") (pinfunction "NC_3_20") (pintype "no_connect"))
    )
    (net (code "149") (name "unconnected-(U4-NC_4-Pad21)") (class "Default")
      (node (ref "U4") (pin "21") (pinfunction "NC_4_21") (pintype "no_connect"))
    )
    (net (code "150") (name "unconnected-(U4-N{slash}C-Pad29)") (class "Default")
      (node (ref "U4") (pin "29") (pinfunction "N/C_29") (pintype "no_connect"))
    )
  )
)
